# sch5_1.net
KiCad netlist of a schematic drawn in Altium Designer
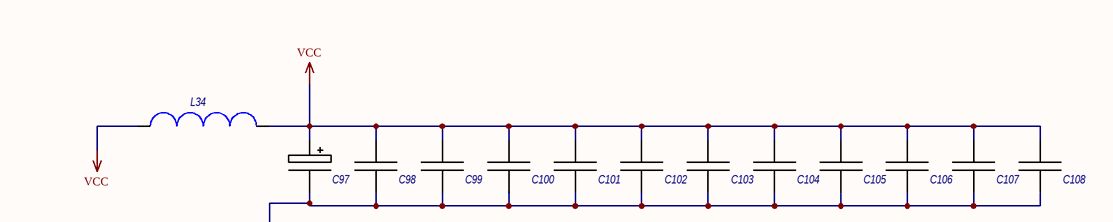
[diagram p0: sch5_1.SchDoc, top left]
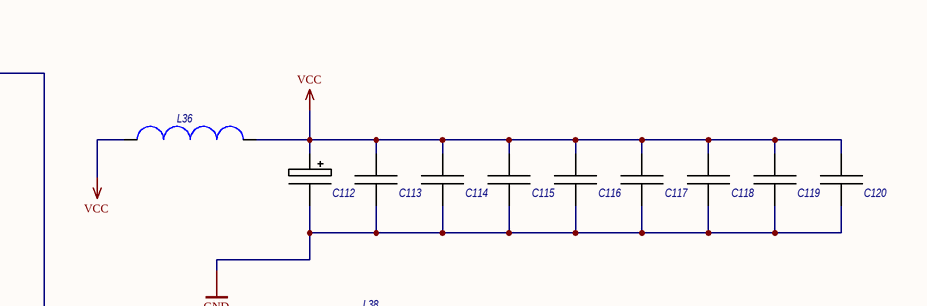
[diagram p1: sch5_1.SchDoc, top right]
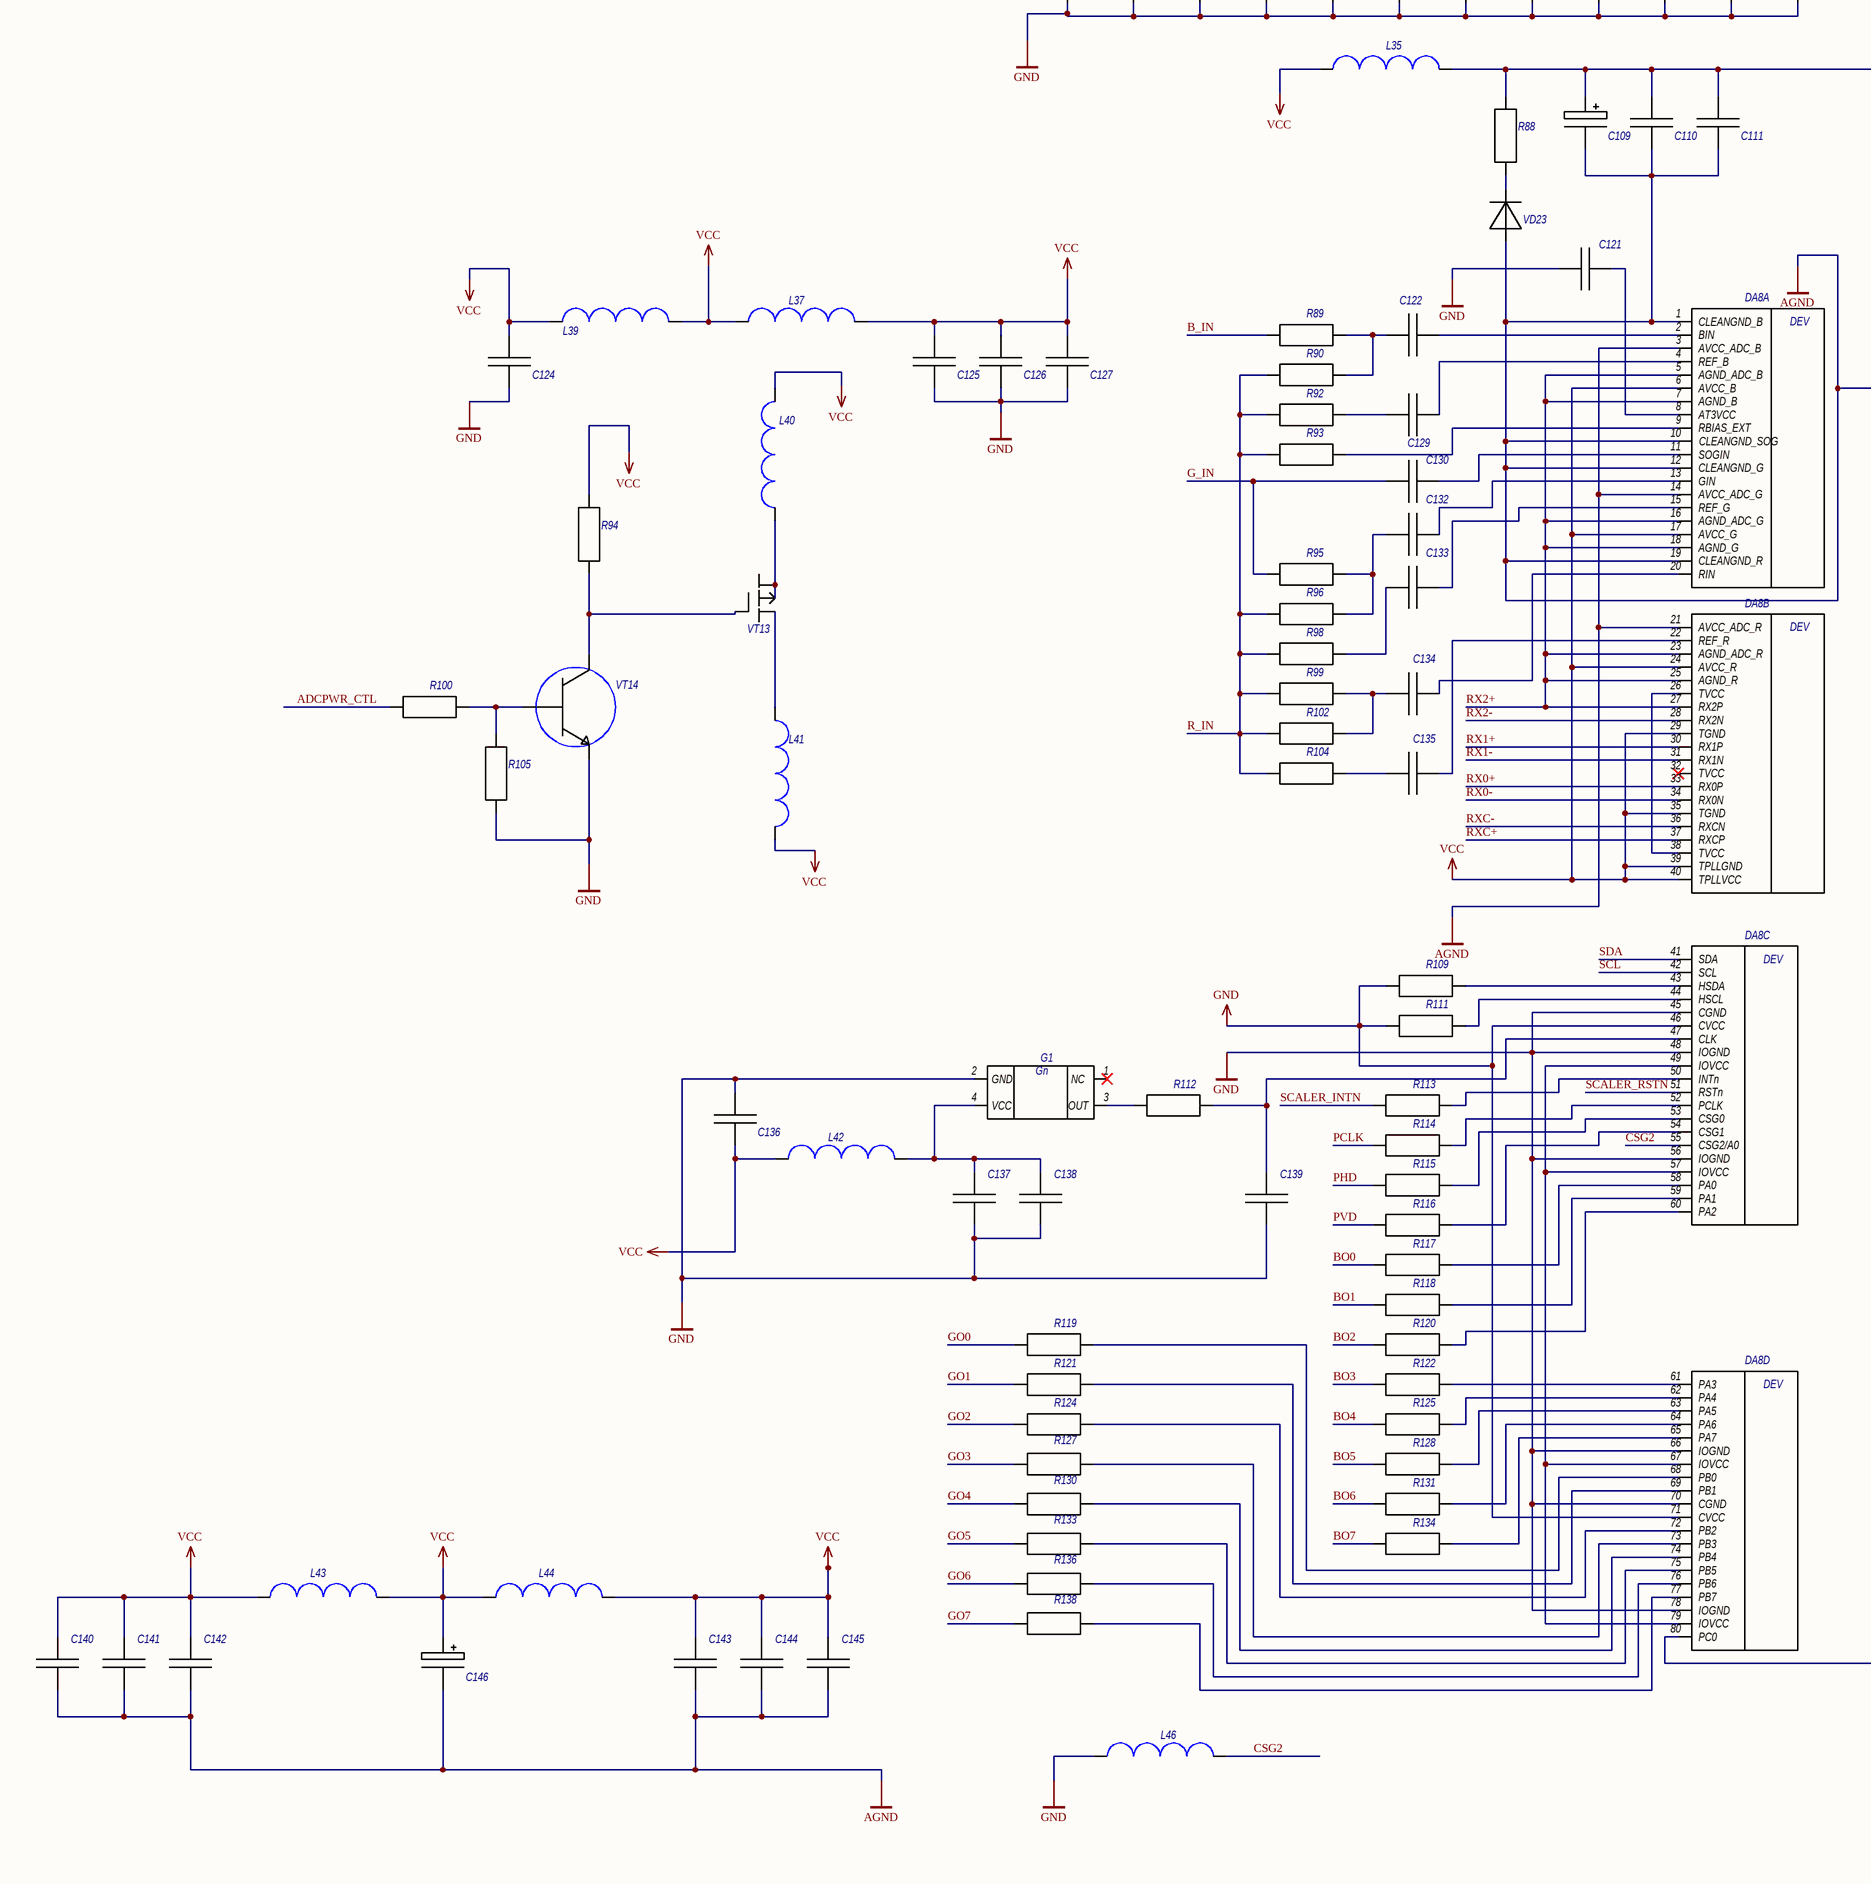
[diagram p2: sch5_1.SchDoc, bottom left]
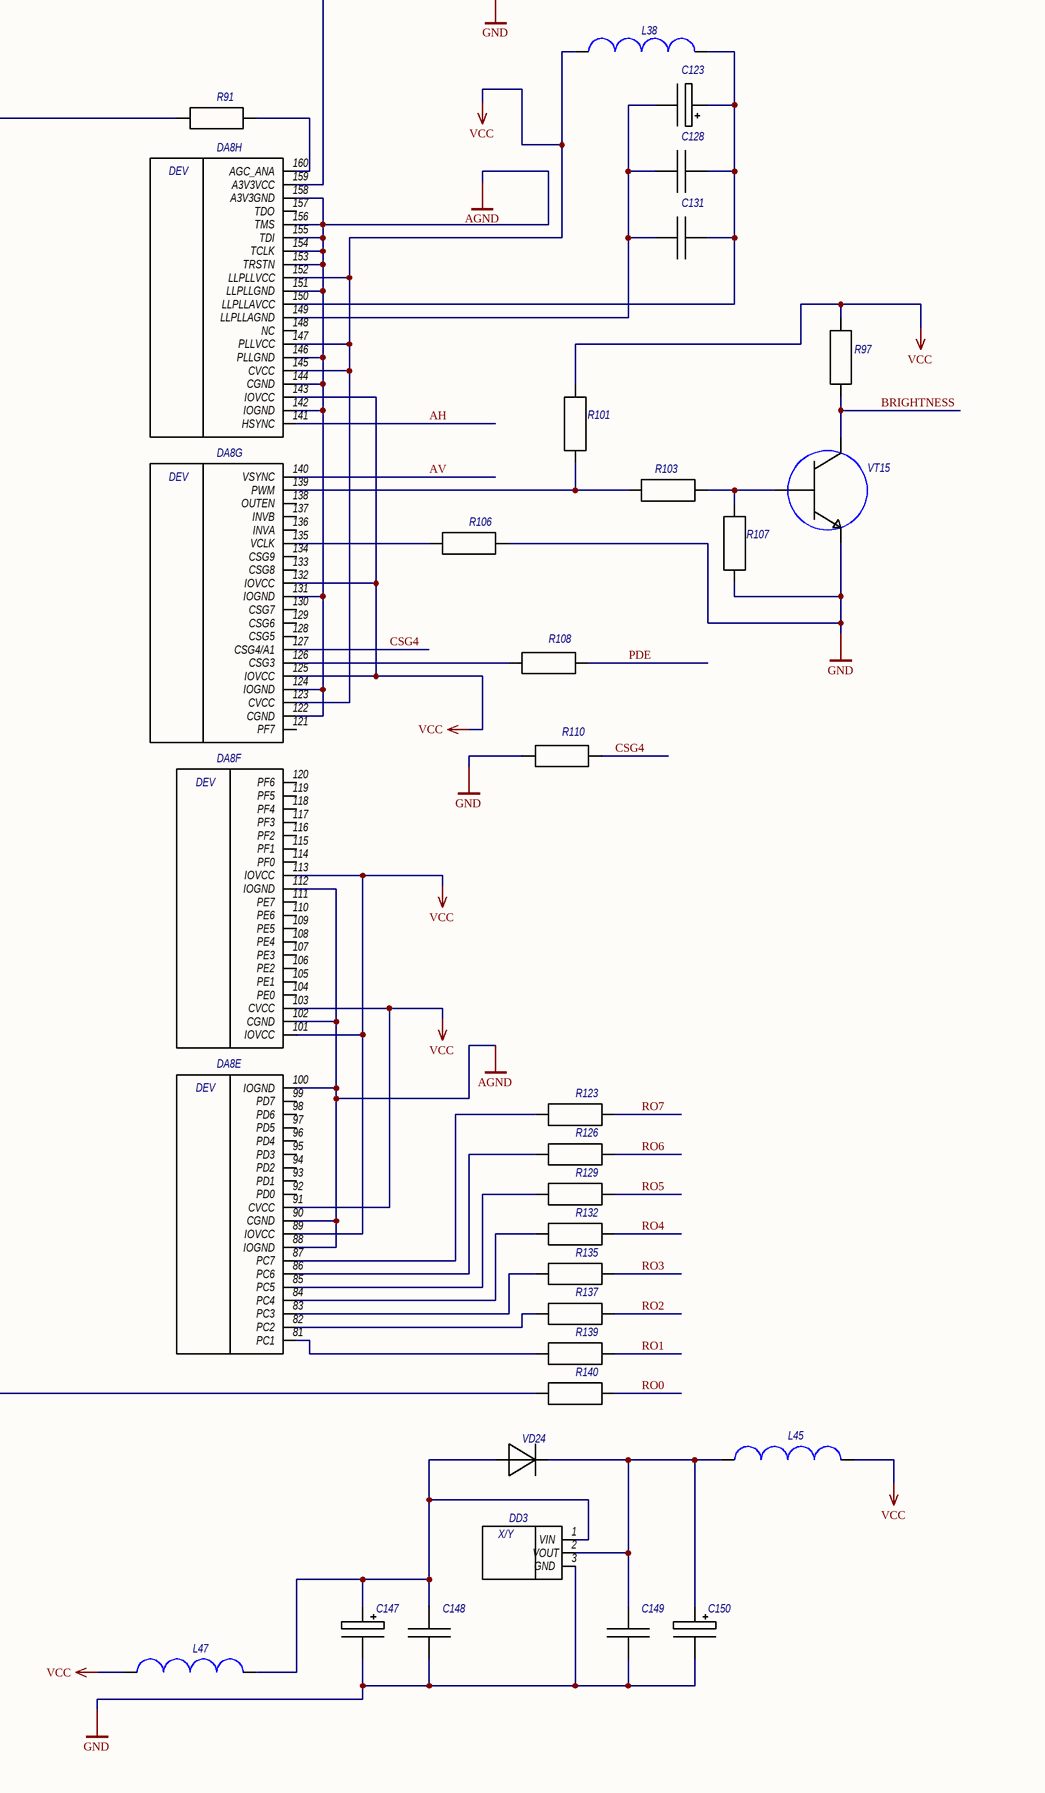
[diagram p3: sch5_1.SchDoc, bottom right]

(export (version "E")
  (design (tool "Eeschema 10.0.6"))
  (components
    (comp (ref "C97")
      (value "*")
      (footprint "Capacitor 0805")
      (libsource (lib "k7shared") (part "Capacitor Duga"))
    )
    (comp (ref "C98")
      (value "*")
      (footprint "Capacitor 0805")
      (libsource (lib "k7shared") (part "Capacitor"))
    )
    (comp (ref "C99")
      (value "*")
      (footprint "Capacitor 0805")
      (libsource (lib "k7shared") (part "Capacitor"))
    )
    (comp (ref "C100")
      (value "*")
      (footprint "Capacitor 0805")
      (libsource (lib "k7shared") (part "Capacitor"))
    )
    (comp (ref "C101")
      (value "*")
      (footprint "Capacitor 0805")
      (libsource (lib "k7shared") (part "Capacitor"))
    )
    (comp (ref "C102")
      (value "*")
      (footprint "Capacitor 0805")
      (libsource (lib "k7shared") (part "Capacitor"))
    )
    (comp (ref "C103")
      (value "*")
      (footprint "Capacitor 0805")
      (libsource (lib "k7shared") (part "Capacitor"))
    )
    (comp (ref "C104")
      (value "*")
      (footprint "Capacitor 0805")
      (libsource (lib "k7shared") (part "Capacitor"))
    )
    (comp (ref "C105")
      (value "*")
      (footprint "Capacitor 0805")
      (libsource (lib "k7shared") (part "Capacitor"))
    )
    (comp (ref "C106")
      (value "*")
      (footprint "Capacitor 0805")
      (libsource (lib "k7shared") (part "Capacitor"))
    )
    (comp (ref "C107")
      (value "*")
      (footprint "Capacitor 0805")
      (libsource (lib "k7shared") (part "Capacitor"))
    )
    (comp (ref "C108")
      (value "*")
      (footprint "Capacitor 0805")
      (libsource (lib "k7shared") (part "Capacitor"))
    )
    (comp (ref "C109")
      (value "*")
      (footprint "Capacitor 0805")
      (libsource (lib "k7shared") (part "Capacitor Duga"))
    )
    (comp (ref "C110")
      (value "*")
      (footprint "Capacitor 0805")
      (libsource (lib "k7shared") (part "Capacitor"))
    )
    (comp (ref "C111")
      (value "*")
      (footprint "Capacitor 0805")
      (libsource (lib "k7shared") (part "Capacitor"))
    )
    (comp (ref "C112")
      (value "*")
      (footprint "Capacitor 0805")
      (libsource (lib "k7shared") (part "Capacitor Duga"))
    )
    (comp (ref "C113")
      (value "*")
      (footprint "Capacitor 0805")
      (libsource (lib "k7shared") (part "Capacitor"))
    )
    (comp (ref "C114")
      (value "*")
      (footprint "Capacitor 0805")
      (libsource (lib "k7shared") (part "Capacitor"))
    )
    (comp (ref "C115")
      (value "*")
      (footprint "Capacitor 0805")
      (libsource (lib "k7shared") (part "Capacitor"))
    )
    (comp (ref "C116")
      (value "*")
      (footprint "Capacitor 0805")
      (libsource (lib "k7shared") (part "Capacitor"))
    )
    (comp (ref "C117")
      (value "*")
      (footprint "Capacitor 0805")
      (libsource (lib "k7shared") (part "Capacitor"))
    )
    (comp (ref "C118")
      (value "*")
      (footprint "Capacitor 0805")
      (libsource (lib "k7shared") (part "Capacitor"))
    )
    (comp (ref "C119")
      (value "*")
      (footprint "Capacitor 0805")
      (libsource (lib "k7shared") (part "Capacitor"))
    )
    (comp (ref "C120")
      (value "*")
      (footprint "Capacitor 0805")
      (libsource (lib "k7shared") (part "Capacitor"))
    )
    (comp (ref "C121")
      (value "*")
      (footprint "Capacitor 0805")
      (libsource (lib "k7shared") (part "Capacitor"))
    )
    (comp (ref "C122")
      (value "*")
      (footprint "Capacitor 0805")
      (libsource (lib "k7shared") (part "Capacitor"))
    )
    (comp (ref "C123")
      (value "*")
      (footprint "Capacitor 0805")
      (libsource (lib "k7shared") (part "Capacitor Duga"))
    )
    (comp (ref "C124")
      (value "*")
      (footprint "Capacitor 0805")
      (libsource (lib "k7shared") (part "Capacitor"))
    )
    (comp (ref "C125")
      (value "*")
      (footprint "Capacitor 0805")
      (libsource (lib "k7shared") (part "Capacitor"))
    )
    (comp (ref "C126")
      (value "*")
      (footprint "Capacitor 0805")
      (libsource (lib "k7shared") (part "Capacitor"))
    )
    (comp (ref "C127")
      (value "*")
      (footprint "Capacitor 0805")
      (libsource (lib "k7shared") (part "Capacitor"))
    )
    (comp (ref "C128")
      (value "*")
      (footprint "Capacitor 0805")
      (libsource (lib "k7shared") (part "Capacitor"))
    )
    (comp (ref "C129")
      (value "*")
      (footprint "Capacitor 0805")
      (libsource (lib "k7shared") (part "Capacitor"))
    )
    (comp (ref "C130")
      (value "*")
      (footprint "Capacitor 0805")
      (libsource (lib "k7shared") (part "Capacitor"))
    )
    (comp (ref "C131")
      (value "*")
      (footprint "Capacitor 0805")
      (libsource (lib "k7shared") (part "Capacitor"))
    )
    (comp (ref "C132")
      (value "*")
      (footprint "Capacitor 0805")
      (libsource (lib "k7shared") (part "Capacitor"))
    )
    (comp (ref "C133")
      (value "*")
      (footprint "Capacitor 0805")
      (libsource (lib "k7shared") (part "Capacitor"))
    )
    (comp (ref "C134")
      (value "*")
      (footprint "Capacitor 0805")
      (libsource (lib "k7shared") (part "Capacitor"))
    )
    (comp (ref "C135")
      (value "*")
      (footprint "Capacitor 0805")
      (libsource (lib "k7shared") (part "Capacitor"))
    )
    (comp (ref "C136")
      (value "*")
      (footprint "Capacitor 0805")
      (libsource (lib "k7shared") (part "Capacitor"))
    )
    (comp (ref "C137")
      (value "*")
      (footprint "Capacitor 0805")
      (libsource (lib "k7shared") (part "Capacitor"))
    )
    (comp (ref "C138")
      (value "*")
      (footprint "Capacitor 0805")
      (libsource (lib "k7shared") (part "Capacitor"))
    )
    (comp (ref "C139")
      (value "*")
      (footprint "Capacitor 0805")
      (libsource (lib "k7shared") (part "Capacitor"))
    )
    (comp (ref "C140")
      (value "*")
      (footprint "Capacitor 0805")
      (libsource (lib "k7shared") (part "Capacitor"))
    )
    (comp (ref "C141")
      (value "*")
      (footprint "Capacitor 0805")
      (libsource (lib "k7shared") (part "Capacitor"))
    )
    (comp (ref "C142")
      (value "*")
      (footprint "Capacitor 0805")
      (libsource (lib "k7shared") (part "Capacitor"))
    )
    (comp (ref "C143")
      (value "*")
      (footprint "Capacitor 0805")
      (libsource (lib "k7shared") (part "Capacitor"))
    )
    (comp (ref "C144")
      (value "*")
      (footprint "Capacitor 0805")
      (libsource (lib "k7shared") (part "Capacitor"))
    )
    (comp (ref "C145")
      (value "*")
      (footprint "Capacitor 0805")
      (libsource (lib "k7shared") (part "Capacitor"))
    )
    (comp (ref "C146")
      (value "*")
      (footprint "Capacitor 0805")
      (libsource (lib "k7shared") (part "Capacitor Duga"))
    )
    (comp (ref "C147")
      (value "*")
      (footprint "Capacitor 0805")
      (libsource (lib "k7shared") (part "Capacitor Duga"))
    )
    (comp (ref "C148")
      (value "*")
      (footprint "Capacitor 0805")
      (libsource (lib "k7shared") (part "Capacitor"))
    )
    (comp (ref "C149")
      (value "*")
      (footprint "Capacitor 0805")
      (libsource (lib "k7shared") (part "Capacitor"))
    )
    (comp (ref "C150")
      (value "*")
      (footprint "Capacitor 0805")
      (libsource (lib "k7shared") (part "Capacitor Duga"))
    )
    (comp (ref "DA8") (value "*") (footprint "OMG_1") (libsource (lib "k7sch5") (part "OMG")))
    (comp (ref "DD3") (value "*") (footprint "MIC39") (libsource (lib "k7sch5") (part "MIC39")))
    (comp (ref "G1") (value "*") (footprint "GENERATOR-25MHZ") (libsource (lib "k7sch5") (part "MHZ25")))
    (comp (ref "L34") (value "*") (footprint "Inductor 2520") (libsource (lib "k7shared") (part "Inductor")))
    (comp (ref "L35") (value "*") (footprint "Inductor 2520") (libsource (lib "k7shared") (part "Inductor")))
    (comp (ref "L36") (value "*") (footprint "Inductor 2520") (libsource (lib "k7shared") (part "Inductor")))
    (comp (ref "L37") (value "*") (footprint "Inductor 2520") (libsource (lib "k7shared") (part "Inductor")))
    (comp (ref "L38") (value "*") (footprint "Inductor 2520") (libsource (lib "k7shared") (part "Inductor")))
    (comp (ref "L39") (value "*") (footprint "Inductor 2520") (libsource (lib "k7shared") (part "Inductor")))
    (comp (ref "L40") (value "*") (footprint "Inductor 2520") (libsource (lib "") (part "Inductor_1")))
    (comp (ref "L41") (value "*") (footprint "Inductor 2520") (libsource (lib "") (part "Inductor_1")))
    (comp (ref "L42") (value "*") (footprint "Inductor 2520") (libsource (lib "k7shared") (part "Inductor")))
    (comp (ref "L43") (value "*") (footprint "Inductor 2520") (libsource (lib "k7shared") (part "Inductor")))
    (comp (ref "L44") (value "*") (footprint "Inductor 2520") (libsource (lib "k7shared") (part "Inductor")))
    (comp (ref "L45") (value "*") (footprint "Inductor 2520") (libsource (lib "k7shared") (part "Inductor")))
    (comp (ref "L46") (value "*") (footprint "Inductor 2520") (libsource (lib "k7shared") (part "Inductor")))
    (comp (ref "L47") (value "*") (footprint "Inductor 2520") (libsource (lib "k7shared") (part "Inductor")))
    (comp (ref "R88") (value "*") (footprint "Resistor 1206") (libsource (lib "k7shared") (part "Resistor")))
    (comp (ref "R89") (value "*") (footprint "Resistor 1206") (libsource (lib "k7shared") (part "Resistor")))
    (comp (ref "R90") (value "*") (footprint "Resistor 1206") (libsource (lib "k7shared") (part "Resistor")))
    (comp (ref "R91") (value "*") (footprint "Resistor 1206") (libsource (lib "k7shared") (part "Resistor")))
    (comp (ref "R92") (value "*") (footprint "Resistor 1206") (libsource (lib "k7shared") (part "Resistor")))
    (comp (ref "R93") (value "*") (footprint "Resistor 1206") (libsource (lib "k7shared") (part "Resistor")))
    (comp (ref "R94") (value "*") (footprint "Resistor 1206") (libsource (lib "k7shared") (part "Resistor")))
    (comp (ref "R95") (value "*") (footprint "Resistor 1206") (libsource (lib "k7shared") (part "Resistor")))
    (comp (ref "R96") (value "*") (footprint "Resistor 1206") (libsource (lib "k7shared") (part "Resistor")))
    (comp (ref "R97") (value "*") (footprint "Resistor 1206") (libsource (lib "k7shared") (part "Resistor")))
    (comp (ref "R98") (value "*") (footprint "Resistor 1206") (libsource (lib "k7shared") (part "Resistor")))
    (comp (ref "R99") (value "*") (footprint "Resistor 1206") (libsource (lib "k7shared") (part "Resistor")))
    (comp (ref "R100") (value "*") (footprint "Resistor 1206") (libsource (lib "k7shared") (part "Resistor")))
    (comp (ref "R101") (value "*") (footprint "Resistor 1206") (libsource (lib "k7shared") (part "Resistor")))
    (comp (ref "R102") (value "*") (footprint "Resistor 1206") (libsource (lib "k7shared") (part "Resistor")))
    (comp (ref "R103") (value "*") (footprint "Resistor 1206") (libsource (lib "k7shared") (part "Resistor")))
    (comp (ref "R104") (value "*") (footprint "Resistor 1206") (libsource (lib "k7shared") (part "Resistor")))
    (comp (ref "R105") (value "*") (footprint "Resistor 1206") (libsource (lib "k7shared") (part "Resistor")))
    (comp (ref "R106") (value "*") (footprint "Resistor 1206") (libsource (lib "k7shared") (part "Resistor")))
    (comp (ref "R107") (value "*") (footprint "Resistor 1206") (libsource (lib "k7shared") (part "Resistor")))
    (comp (ref "R108") (value "*") (footprint "Resistor 1206") (libsource (lib "k7shared") (part "Resistor")))
    (comp (ref "R109") (value "*") (footprint "Resistor 1206") (libsource (lib "k7shared") (part "Resistor")))
    (comp (ref "R110") (value "*") (footprint "Resistor 1206") (libsource (lib "k7shared") (part "Resistor")))
    (comp (ref "R111") (value "*") (footprint "Resistor 1206") (libsource (lib "k7shared") (part "Resistor")))
    (comp (ref "R112") (value "*") (footprint "Resistor 1206") (libsource (lib "k7shared") (part "Resistor")))
    (comp (ref "R113") (value "*") (footprint "Resistor 1206") (libsource (lib "k7shared") (part "Resistor")))
    (comp (ref "R114") (value "*") (footprint "Resistor 1206") (libsource (lib "k7shared") (part "Resistor")))
    (comp (ref "R115") (value "*") (footprint "Resistor 1206") (libsource (lib "k7shared") (part "Resistor")))
    (comp (ref "R116") (value "*") (footprint "Resistor 1206") (libsource (lib "k7shared") (part "Resistor")))
    (comp (ref "R117") (value "*") (footprint "Resistor 1206") (libsource (lib "k7shared") (part "Resistor")))
    (comp (ref "R118") (value "*") (footprint "Resistor 1206") (libsource (lib "k7shared") (part "Resistor")))
    (comp (ref "R119") (value "*") (footprint "Resistor 1206") (libsource (lib "k7shared") (part "Resistor")))
    (comp (ref "R120") (value "*") (footprint "Resistor 1206") (libsource (lib "k7shared") (part "Resistor")))
    (comp (ref "R121") (value "*") (footprint "Resistor 1206") (libsource (lib "k7shared") (part "Resistor")))
    (comp (ref "R122") (value "*") (footprint "Resistor 1206") (libsource (lib "k7shared") (part "Resistor")))
    (comp (ref "R123") (value "*") (footprint "Resistor 1206") (libsource (lib "k7shared") (part "Resistor")))
    (comp (ref "R124") (value "*") (footprint "Resistor 1206") (libsource (lib "k7shared") (part "Resistor")))
    (comp (ref "R125") (value "*") (footprint "Resistor 1206") (libsource (lib "k7shared") (part "Resistor")))
    (comp (ref "R126") (value "*") (footprint "Resistor 1206") (libsource (lib "k7shared") (part "Resistor")))
    (comp (ref "R127") (value "*") (footprint "Resistor 1206") (libsource (lib "k7shared") (part "Resistor")))
    (comp (ref "R128") (value "*") (footprint "Resistor 1206") (libsource (lib "k7shared") (part "Resistor")))
    (comp (ref "R129") (value "*") (footprint "Resistor 1206") (libsource (lib "k7shared") (part "Resistor")))
    (comp (ref "R130") (value "*") (footprint "Resistor 1206") (libsource (lib "k7shared") (part "Resistor")))
    (comp (ref "R131") (value "*") (footprint "Resistor 1206") (libsource (lib "k7shared") (part "Resistor")))
    (comp (ref "R132") (value "*") (footprint "Resistor 1206") (libsource (lib "k7shared") (part "Resistor")))
    (comp (ref "R133") (value "*") (footprint "Resistor 1206") (libsource (lib "k7shared") (part "Resistor")))
    (comp (ref "R134") (value "*") (footprint "Resistor 1206") (libsource (lib "k7shared") (part "Resistor")))
    (comp (ref "R135") (value "*") (footprint "Resistor 1206") (libsource (lib "k7shared") (part "Resistor")))
    (comp (ref "R136") (value "*") (footprint "Resistor 1206") (libsource (lib "k7shared") (part "Resistor")))
    (comp (ref "R137") (value "*") (footprint "Resistor 1206") (libsource (lib "k7shared") (part "Resistor")))
    (comp (ref "R138") (value "*") (footprint "Resistor 1206") (libsource (lib "k7shared") (part "Resistor")))
    (comp (ref "R139") (value "*") (footprint "Resistor 1206") (libsource (lib "k7shared") (part "Resistor")))
    (comp (ref "R140") (value "*") (footprint "Resistor 1206") (libsource (lib "k7shared") (part "Resistor")))
    (comp (ref "VD23") (value "*") (footprint "Diode") (libsource (lib "k7shared") (part "Diode 1")))
    (comp (ref "VD24") (value "*") (footprint "Diode") (libsource (lib "k7shared") (part "Diode 1")))
    (comp (ref "VT13")
      (value "MOP TRANSISTOR")
      (footprint "TR")
      (libsource (lib "k7shared") (part "MOP TRANSISTOR"))
    )
    (comp (ref "VT14")
      (value "*")
      (footprint "Transistor 1")
      (libsource (lib "k7shared") (part "Transistor 1"))
    )
    (comp (ref "VT15")
      (value "*")
      (footprint "Transistor 1")
      (libsource (lib "k7shared") (part "Transistor 1"))
    )
  )
  (nets
    (net (code "1") (name "/ADCPWR_CTL") (class "Default")
      (node (ref "R100") (pin "1") (pinfunction "1_1") (pintype "passive"))
    )
    (net (code "2") (name "/AH") (class "Default")
      (node (ref "DA8") (pin "141") (pinfunction "HSYNC_141") (pintype "passive"))
    )
    (net (code "3") (name "/AV") (class "Default")
      (node (ref "DA8") (pin "140") (pinfunction "VSYNC_140") (pintype "passive"))
    )
    (net (code "4") (name "/BO0") (class "Default")
      (node (ref "R117") (pin "1") (pinfunction "1_1") (pintype "passive"))
    )
    (net (code "5") (name "/BO1") (class "Default")
      (node (ref "R118") (pin "1") (pinfunction "1_1") (pintype "passive"))
    )
    (net (code "6") (name "/BO2") (class "Default")
      (node (ref "R120") (pin "1") (pinfunction "1_1") (pintype "passive"))
    )
    (net (code "7") (name "/BO3") (class "Default")
      (node (ref "R122") (pin "1") (pinfunction "1_1") (pintype "passive"))
    )
    (net (code "8") (name "/BO4") (class "Default")
      (node (ref "R125") (pin "1") (pinfunction "1_1") (pintype "passive"))
    )
    (net (code "9") (name "/BO5") (class "Default")
      (node (ref "R128") (pin "1") (pinfunction "1_1") (pintype "passive"))
    )
    (net (code "10") (name "/BO6") (class "Default")
      (node (ref "R131") (pin "1") (pinfunction "1_1") (pintype "passive"))
    )
    (net (code "11") (name "/BO7") (class "Default")
      (node (ref "R134") (pin "1") (pinfunction "1_1") (pintype "passive"))
    )
    (net (code "12") (name "/BRIGHTNESS") (class "Default")
      (node (ref "R97") (pin "1") (pinfunction "1_1") (pintype "passive"))
      (node (ref "VT15") (pin "2") (pinfunction "EMITTER_2") (pintype "passive"))
    )
    (net (code "13") (name "/B_IN") (class "Default")
      (node (ref "R89") (pin "1") (pinfunction "1_1") (pintype "passive"))
    )
    (net (code "14") (name "/CSG2") (class "Default")
      (node (ref "DA8") (pin "55") (pinfunction "CSG2/A0_55") (pintype "passive"))
      (node (ref "L46") (pin "2") (pinfunction "2_2") (pintype "passive"))
    )
    (net (code "15") (name "/CSG4") (class "Default")
      (node (ref "DA8") (pin "127") (pinfunction "CSG4/A1_127") (pintype "passive"))
      (node (ref "R110") (pin "2") (pinfunction "2_2") (pintype "passive"))
    )
    (net (code "16") (name "/GO0") (class "Default")
      (node (ref "R119") (pin "1") (pinfunction "1_1") (pintype "passive"))
    )
    (net (code "17") (name "/GO1") (class "Default")
      (node (ref "R121") (pin "1") (pinfunction "1_1") (pintype "passive"))
    )
    (net (code "18") (name "/GO2") (class "Default")
      (node (ref "R124") (pin "1") (pinfunction "1_1") (pintype "passive"))
    )
    (net (code "19") (name "/GO3") (class "Default")
      (node (ref "R127") (pin "1") (pinfunction "1_1") (pintype "passive"))
    )
    (net (code "20") (name "/GO4") (class "Default")
      (node (ref "R130") (pin "1") (pinfunction "1_1") (pintype "passive"))
    )
    (net (code "21") (name "/GO5") (class "Default")
      (node (ref "R133") (pin "1") (pinfunction "1_1") (pintype "passive"))
    )
    (net (code "22") (name "/GO6") (class "Default")
      (node (ref "R136") (pin "1") (pinfunction "1_1") (pintype "passive"))
    )
    (net (code "23") (name "/GO7") (class "Default")
      (node (ref "R138") (pin "1") (pinfunction "1_1") (pintype "passive"))
    )
    (net (code "24") (name "/G_IN") (class "Default")
      (node (ref "C130") (pin "2") (pinfunction "2_2") (pintype "passive"))
      (node (ref "R95") (pin "1") (pinfunction "1_1") (pintype "passive"))
    )
    (net (code "25") (name "/PCLK") (class "Default")
      (node (ref "R114") (pin "1") (pinfunction "1_1") (pintype "passive"))
    )
    (net (code "26") (name "/PDE") (class "Default")
      (node (ref "R108") (pin "2") (pinfunction "2_2") (pintype "passive"))
    )
    (net (code "27") (name "/PHD") (class "Default")
      (node (ref "R115") (pin "1") (pinfunction "1_1") (pintype "passive"))
    )
    (net (code "28") (name "/PVD") (class "Default")
      (node (ref "R116") (pin "1") (pinfunction "1_1") (pintype "passive"))
    )
    (net (code "29") (name "/RO0") (class "Default")
      (node (ref "R140") (pin "2") (pinfunction "2_2") (pintype "passive"))
    )
    (net (code "30") (name "/RO1") (class "Default")
      (node (ref "R139") (pin "2") (pinfunction "2_2") (pintype "passive"))
    )
    (net (code "31") (name "/RO2") (class "Default")
      (node (ref "R137") (pin "2") (pinfunction "2_2") (pintype "passive"))
    )
    (net (code "32") (name "/RO3") (class "Default")
      (node (ref "R135") (pin "2") (pinfunction "2_2") (pintype "passive"))
    )
    (net (code "33") (name "/RO4") (class "Default")
      (node (ref "R132") (pin "2") (pinfunction "2_2") (pintype "passive"))
    )
    (net (code "34") (name "/RO5") (class "Default")
      (node (ref "R129") (pin "2") (pinfunction "2_2") (pintype "passive"))
    )
    (net (code "35") (name "/RO6") (class "Default")
      (node (ref "R126") (pin "2") (pinfunction "2_2") (pintype "passive"))
    )
    (net (code "36") (name "/RO7") (class "Default")
      (node (ref "R123") (pin "2") (pinfunction "2_2") (pintype "passive"))
    )
    (net (code "37") (name "/RX0+") (class "Default")
      (node (ref "DA8") (pin "33") (pinfunction "RX0P_33") (pintype "passive"))
    )
    (net (code "38") (name "/RX0-") (class "Default")
      (node (ref "DA8") (pin "34") (pinfunction "RX0N_34") (pintype "passive"))
    )
    (net (code "39") (name "/RX1+") (class "Default")
      (node (ref "DA8") (pin "30") (pinfunction "RX1P_30") (pintype "passive"))
    )
    (net (code "40") (name "/RX1-") (class "Default")
      (node (ref "DA8") (pin "31") (pinfunction "RX1N_31") (pintype "passive"))
    )
    (net (code "41") (name "/RX2+") (class "Default")
      (node (ref "DA8") (pin "16") (pinfunction "AGND_ADC_G_16") (pintype "passive"))
      (node (ref "DA8") (pin "18") (pinfunction "AGND_G_18") (pintype "passive"))
      (node (ref "DA8") (pin "23") (pinfunction "AGND_ADC_R_23") (pintype "passive"))
      (node (ref "DA8") (pin "25") (pinfunction "AGND_R_25") (pintype "passive"))
      (node (ref "DA8") (pin "27") (pinfunction "RX2P_27") (pintype "passive"))
      (node (ref "DA8") (pin "5") (pinfunction "AGND_ADC_B_5") (pintype "passive"))
      (node (ref "DA8") (pin "7") (pinfunction "AGND_B_7") (pintype "passive"))
    )
    (net (code "42") (name "/RX2-") (class "Default")
      (node (ref "DA8") (pin "28") (pinfunction "RX2N_28") (pintype "passive"))
    )
    (net (code "43") (name "/RXC+") (class "Default")
      (node (ref "DA8") (pin "37") (pinfunction "RXCP_37") (pintype "passive"))
    )
    (net (code "44") (name "/RXC-") (class "Default")
      (node (ref "DA8") (pin "36") (pinfunction "RXCN_36") (pintype "passive"))
    )
    (net (code "45") (name "/R_IN") (class "Default")
      (node (ref "R102") (pin "1") (pinfunction "1_1") (pintype "passive"))
      (node (ref "R104") (pin "1") (pinfunction "1_1") (pintype "passive"))
      (node (ref "R90") (pin "1") (pinfunction "1_1") (pintype "passive"))
      (node (ref "R92") (pin "1") (pinfunction "1_1") (pintype "passive"))
      (node (ref "R93") (pin "1") (pinfunction "1_1") (pintype "passive"))
      (node (ref "R96") (pin "1") (pinfunction "1_1") (pintype "passive"))
      (node (ref "R98") (pin "1") (pinfunction "1_1") (pintype "passive"))
      (node (ref "R99") (pin "1") (pinfunction "1_1") (pintype "passive"))
    )
    (net (code "46") (name "/SCALER_INTN") (class "Default")
      (node (ref "R113") (pin "1") (pinfunction "1_1") (pintype "passive"))
    )
    (net (code "47") (name "/SCALER_RSTN") (class "Default")
      (node (ref "DA8") (pin "51") (pinfunction "RSTn_51") (pintype "passive"))
    )
    (net (code "48") (name "/SCL") (class "Default")
      (node (ref "DA8") (pin "42") (pinfunction "SCL_42") (pintype "passive"))
    )
    (net (code "49") (name "/SDA") (class "Default")
      (node (ref "DA8") (pin "41") (pinfunction "SDA_41") (pintype "passive"))
    )
    (net (code "50") (name "AGND") (class "Default")
      (node (ref "C109") (pin "1") (pinfunction "1_1") (pintype "passive"))
      (node (ref "C110") (pin "1") (pinfunction "1_1") (pintype "passive"))
      (node (ref "C111") (pin "1") (pinfunction "1_1") (pintype "passive"))
      (node (ref "C140") (pin "1") (pinfunction "1_1") (pintype "passive"))
      (node (ref "C141") (pin "1") (pinfunction "1_1") (pintype "passive"))
      (node (ref "C142") (pin "1") (pinfunction "1_1") (pintype "passive"))
      (node (ref "C143") (pin "1") (pinfunction "1_1") (pintype "passive"))
      (node (ref "C144") (pin "1") (pinfunction "1_1") (pintype "passive"))
      (node (ref "C145") (pin "1") (pinfunction "1_1") (pintype "passive"))
      (node (ref "C146") (pin "1") (pinfunction "1_1") (pintype "passive"))
      (node (ref "DA8") (pin "1") (pinfunction "CLEANGND_B_1") (pintype "passive"))
      (node (ref "DA8") (pin "10") (pinfunction "CLEANGND_SOG_10") (pintype "passive"))
      (node (ref "DA8") (pin "100") (pinfunction "IOGND_100") (pintype "passive"))
      (node (ref "DA8") (pin "102") (pinfunction "CGND_102") (pintype "passive"))
      (node (ref "DA8") (pin "112") (pinfunction "IOGND_112") (pintype "passive"))
      (node (ref "DA8") (pin "12") (pinfunction "CLEANGND_G_12") (pintype "passive"))
      (node (ref "DA8") (pin "122") (pinfunction "CGND_122") (pintype "passive"))
      (node (ref "DA8") (pin "124") (pinfunction "IOGND_124") (pintype "passive"))
      (node (ref "DA8") (pin "131") (pinfunction "IOGND_131") (pintype "passive"))
      (node (ref "DA8") (pin "14") (pinfunction "AVCC_ADC_G_14") (pintype "passive"))
      (node (ref "DA8") (pin "142") (pinfunction "IOGND_142") (pintype "passive"))
      (node (ref "DA8") (pin "144") (pinfunction "CGND_144") (pintype "passive"))
      (node (ref "DA8") (pin "146") (pinfunction "PLLGND_146") (pintype "passive"))
      (node (ref "DA8") (pin "151") (pinfunction "LLPLLGND_151") (pintype "passive"))
      (node (ref "DA8") (pin "153") (pinfunction "TRSTN_153") (pintype "passive"))
      (node (ref "DA8") (pin "154") (pinfunction "TCLK_154") (pintype "passive"))
      (node (ref "DA8") (pin "155") (pinfunction "TDI_155") (pintype "passive"))
      (node (ref "DA8") (pin "156") (pinfunction "TMS_156") (pintype "passive"))
      (node (ref "DA8") (pin "158") (pinfunction "A3V3GND_158") (pintype "passive"))
      (node (ref "DA8") (pin "19") (pinfunction "CLEANGND_R_19") (pintype "passive"))
      (node (ref "DA8") (pin "21") (pinfunction "AVCC_ADC_R_21") (pintype "passive"))
      (node (ref "DA8") (pin "3") (pinfunction "AVCC_ADC_B_3") (pintype "passive"))
      (node (ref "DA8") (pin "88") (pinfunction "IOGND_88") (pintype "passive"))
      (node (ref "DA8") (pin "90") (pinfunction "CGND_90") (pintype "passive"))
      (node (ref "R91") (pin "1") (pinfunction "1_1") (pintype "passive"))
      (node (ref "VD23") (pin "1") (pinfunction "1_1") (pintype "passive"))
    )
    (net (code "51") (name "GND") (class "Default")
      (node (ref "C100") (pin "1") (pinfunction "1_1") (pintype "passive"))
      (node (ref "C101") (pin "1") (pinfunction "1_1") (pintype "passive"))
      (node (ref "C102") (pin "1") (pinfunction "1_1") (pintype "passive"))
      (node (ref "C103") (pin "1") (pinfunction "1_1") (pintype "passive"))
      (node (ref "C104") (pin "1") (pinfunction "1_1") (pintype "passive"))
      (node (ref "C105") (pin "1") (pinfunction "1_1") (pintype "passive"))
      (node (ref "C106") (pin "1") (pinfunction "1_1") (pintype "passive"))
      (node (ref "C107") (pin "1") (pinfunction "1_1") (pintype "passive"))
      (node (ref "C108") (pin "1") (pinfunction "1_1") (pintype "passive"))
      (node (ref "C112") (pin "1") (pinfunction "1_1") (pintype "passive"))
      (node (ref "C113") (pin "1") (pinfunction "1_1") (pintype "passive"))
      (node (ref "C114") (pin "1") (pinfunction "1_1") (pintype "passive"))
      (node (ref "C115") (pin "1") (pinfunction "1_1") (pintype "passive"))
      (node (ref "C116") (pin "1") (pinfunction "1_1") (pintype "passive"))
      (node (ref "C117") (pin "1") (pinfunction "1_1") (pintype "passive"))
      (node (ref "C118") (pin "1") (pinfunction "1_1") (pintype "passive"))
      (node (ref "C119") (pin "1") (pinfunction "1_1") (pintype "passive"))
      (node (ref "C120") (pin "1") (pinfunction "1_1") (pintype "passive"))
      (node (ref "C121") (pin "2") (pinfunction "2_2") (pintype "passive"))
      (node (ref "C124") (pin "1") (pinfunction "1_1") (pintype "passive"))
      (node (ref "C125") (pin "1") (pinfunction "1_1") (pintype "passive"))
      (node (ref "C126") (pin "1") (pinfunction "1_1") (pintype "passive"))
      (node (ref "C127") (pin "1") (pinfunction "1_1") (pintype "passive"))
      (node (ref "C136") (pin "2") (pinfunction "2_2") (pintype "passive"))
      (node (ref "C137") (pin "1") (pinfunction "1_1") (pintype "passive"))
      (node (ref "C138") (pin "1") (pinfunction "1_1") (pintype "passive"))
      (node (ref "C139") (pin "1") (pinfunction "1_1") (pintype "passive"))
      (node (ref "C147") (pin "1") (pinfunction "1_1") (pintype "passive"))
      (node (ref "C148") (pin "1") (pinfunction "1_1") (pintype "passive"))
      (node (ref "C149") (pin "1") (pinfunction "1_1") (pintype "passive"))
      (node (ref "C150") (pin "1") (pinfunction "1_1") (pintype "passive"))
      (node (ref "C97") (pin "1") (pinfunction "1_1") (pintype "passive"))
      (node (ref "C98") (pin "1") (pinfunction "1_1") (pintype "passive"))
      (node (ref "C99") (pin "1") (pinfunction "1_1") (pintype "passive"))
      (node (ref "DA8") (pin "45") (pinfunction "CGND_45") (pintype "passive"))
      (node (ref "DA8") (pin "46") (pinfunction "CVCC_46") (pintype "passive"))
      (node (ref "DA8") (pin "48") (pinfunction "IOGND_48") (pintype "passive"))
      (node (ref "DA8") (pin "56") (pinfunction "IOGND_56") (pintype "passive"))
      (node (ref "DA8") (pin "66") (pinfunction "IOGND_66") (pintype "passive"))
      (node (ref "DA8") (pin "70") (pinfunction "CGND_70") (pintype "passive"))
      (node (ref "DA8") (pin "71") (pinfunction "CVCC_71") (pintype "passive"))
      (node (ref "DA8") (pin "78") (pinfunction "IOGND_78") (pintype "passive"))
      (node (ref "DD3") (pin "3") (pinfunction "GND_3") (pintype "passive"))
      (node (ref "G1") (pin "2") (pinfunction "GND_2") (pintype "passive"))
      (node (ref "L46") (pin "1") (pinfunction "1_1") (pintype "passive"))
      (node (ref "R105") (pin "1") (pinfunction "1_1") (pintype "passive"))
      (node (ref "R106") (pin "2") (pinfunction "2_2") (pintype "passive"))
      (node (ref "R107") (pin "1") (pinfunction "1_1") (pintype "passive"))
      (node (ref "R109") (pin "1") (pinfunction "1_1") (pintype "passive"))
      (node (ref "R110") (pin "1") (pinfunction "1_1") (pintype "passive"))
      (node (ref "R111") (pin "1") (pinfunction "1_1") (pintype "passive"))
      (node (ref "VT14") (pin "1") (pinfunction "KOLLECTOR_1") (pintype "passive"))
      (node (ref "VT15") (pin "1") (pinfunction "KOLLECTOR_1") (pintype "passive"))
    )
    (net (code "52") (name "Net-(C122-Pad2)") (class "Default")
      (node (ref "C122") (pin "2") (pinfunction "2_2") (pintype "passive"))
      (node (ref "R89") (pin "2") (pinfunction "2_2") (pintype "passive"))
      (node (ref "R90") (pin "2") (pinfunction "2_2") (pintype "passive"))
    )
    (net (code "53") (name "Net-(C129-Pad2)") (class "Default")
      (node (ref "C129") (pin "2") (pinfunction "2_2") (pintype "passive"))
      (node (ref "R92") (pin "2") (pinfunction "2_2") (pintype "passive"))
    )
    (net (code "54") (name "Net-(C132-Pad2)") (class "Default")
      (node (ref "C132") (pin "2") (pinfunction "2_2") (pintype "passive"))
      (node (ref "R95") (pin "2") (pinfunction "2_2") (pintype "passive"))
      (node (ref "R96") (pin "2") (pinfunction "2_2") (pintype "passive"))
    )
    (net (code "55") (name "Net-(C133-Pad2)") (class "Default")
      (node (ref "C133") (pin "2") (pinfunction "2_2") (pintype "passive"))
      (node (ref "R98") (pin "2") (pinfunction "2_2") (pintype "passive"))
    )
    (net (code "56") (name "Net-(C134-Pad2)") (class "Default")
      (node (ref "C134") (pin "2") (pinfunction "2_2") (pintype "passive"))
      (node (ref "R102") (pin "2") (pinfunction "2_2") (pintype "passive"))
      (node (ref "R99") (pin "2") (pinfunction "2_2") (pintype "passive"))
    )
    (net (code "57") (name "Net-(C135-Pad2)") (class "Default")
      (node (ref "C135") (pin "2") (pinfunction "2_2") (pintype "passive"))
      (node (ref "R104") (pin "2") (pinfunction "2_2") (pintype "passive"))
    )
    (net (code "58") (name "Net-(DA8A-AT3VCC)") (class "Default")
      (node (ref "C121") (pin "1") (pinfunction "1_1") (pintype "passive"))
      (node (ref "DA8") (pin "8") (pinfunction "AT3VCC_8") (pintype "passive"))
    )
    (net (code "59") (name "Net-(DA8A-BIN)") (class "Default")
      (node (ref "C122") (pin "1") (pinfunction "1_1") (pintype "passive"))
      (node (ref "DA8") (pin "2") (pinfunction "BIN_2") (pintype "passive"))
    )
    (net (code "60") (name "Net-(DA8A-GIN)") (class "Default")
      (node (ref "C132") (pin "1") (pinfunction "1_1") (pintype "passive"))
      (node (ref "DA8") (pin "13") (pinfunction "GIN_13") (pintype "passive"))
    )
    (net (code "61") (name "Net-(DA8A-RBIAS_EXT)") (class "Default")
      (node (ref "DA8") (pin "9") (pinfunction "RBIAS_EXT_9") (pintype "passive"))
      (node (ref "R93") (pin "2") (pinfunction "2_2") (pintype "passive"))
    )
    (net (code "62") (name "Net-(DA8A-REF_B)") (class "Default")
      (node (ref "C129") (pin "1") (pinfunction "1_1") (pintype "passive"))
      (node (ref "DA8") (pin "4") (pinfunction "REF_B_4") (pintype "passive"))
    )
    (net (code "63") (name "Net-(DA8A-REF_G)") (class "Default")
      (node (ref "C133") (pin "1") (pinfunction "1_1") (pintype "passive"))
      (node (ref "DA8") (pin "15") (pinfunction "REF_G_15") (pintype "passive"))
    )
    (net (code "64") (name "Net-(DA8A-RIN)") (class "Default")
      (node (ref "C134") (pin "1") (pinfunction "1_1") (pintype "passive"))
      (node (ref "DA8") (pin "20") (pinfunction "RIN_20") (pintype "passive"))
    )
    (net (code "65") (name "Net-(DA8A-SOGIN)") (class "Default")
      (node (ref "C130") (pin "1") (pinfunction "1_1") (pintype "passive"))
      (node (ref "DA8") (pin "11") (pinfunction "SOGIN_11") (pintype "passive"))
    )
    (net (code "66") (name "Net-(DA8B-REF_R)") (class "Default")
      (node (ref "C135") (pin "1") (pinfunction "1_1") (pintype "passive"))
      (node (ref "DA8") (pin "22") (pinfunction "REF_R_22") (pintype "passive"))
    )
    (net (code "67") (name "Net-(DA8B-TVCC-Pad26)") (class "Default")
      (node (ref "DA8") (pin "26") (pinfunction "TVCC_26") (pintype "passive"))
      (node (ref "DA8") (pin "38") (pinfunction "TVCC_38") (pintype "passive"))
    )
    (net (code "68") (name "Net-(DA8C-CLK)") (class "Default")
      (node (ref "C139") (pin "2") (pinfunction "2_2") (pintype "passive"))
      (node (ref "DA8") (pin "47") (pinfunction "CLK_47") (pintype "passive"))
      (node (ref "R112") (pin "2") (pinfunction "2_2") (pintype "passive"))
    )
    (net (code "69") (name "Net-(DA8C-CSG0)") (class "Default")
      (node (ref "DA8") (pin "53") (pinfunction "CSG0_53") (pintype "passive"))
      (node (ref "R115") (pin "2") (pinfunction "2_2") (pintype "passive"))
    )
    (net (code "70") (name "Net-(DA8C-CSG1)") (class "Default")
      (node (ref "DA8") (pin "54") (pinfunction "CSG1_54") (pintype "passive"))
      (node (ref "R116") (pin "2") (pinfunction "2_2") (pintype "passive"))
    )
    (net (code "71") (name "Net-(DA8C-HSCL)") (class "Default")
      (node (ref "DA8") (pin "44") (pinfunction "HSCL_44") (pintype "passive"))
      (node (ref "R111") (pin "2") (pinfunction "2_2") (pintype "passive"))
    )
    (net (code "72") (name "Net-(DA8C-HSDA)") (class "Default")
      (node (ref "DA8") (pin "43") (pinfunction "HSDA_43") (pintype "passive"))
      (node (ref "R109") (pin "2") (pinfunction "2_2") (pintype "passive"))
    )
    (net (code "73") (name "Net-(DA8C-INTn)") (class "Default")
      (node (ref "DA8") (pin "50") (pinfunction "INTn_50") (pintype "passive"))
      (node (ref "R113") (pin "2") (pinfunction "2_2") (pintype "passive"))
    )
    (net (code "74") (name "Net-(DA8C-IOVCC-Pad49)") (class "Default")
      (node (ref "DA8") (pin "49") (pinfunction "IOVCC_49") (pintype "passive"))
      (node (ref "DA8") (pin "57") (pinfunction "IOVCC_57") (pintype "passive"))
      (node (ref "DA8") (pin "67") (pinfunction "IOVCC_67") (pintype "passive"))
      (node (ref "DA8") (pin "79") (pinfunction "IOVCC_79") (pintype "passive"))
    )
    (net (code "75") (name "Net-(DA8C-PA0)") (class "Default")
      (node (ref "DA8") (pin "58") (pinfunction "PA0_58") (pintype "passive"))
      (node (ref "R117") (pin "2") (pinfunction "2_2") (pintype "passive"))
    )
    (net (code "76") (name "Net-(DA8C-PA1)") (class "Default")
      (node (ref "DA8") (pin "59") (pinfunction "PA1_59") (pintype "passive"))
      (node (ref "R118") (pin "2") (pinfunction "2_2") (pintype "passive"))
    )
    (net (code "77") (name "Net-(DA8C-PA2)") (class "Default")
      (node (ref "DA8") (pin "60") (pinfunction "PA2_60") (pintype "passive"))
      (node (ref "R120") (pin "2") (pinfunction "2_2") (pintype "passive"))
    )
    (net (code "78") (name "Net-(DA8C-PCLK)") (class "Default")
      (node (ref "DA8") (pin "52") (pinfunction "PCLK_52") (pintype "passive"))
      (node (ref "R114") (pin "2") (pinfunction "2_2") (pintype "passive"))
    )
    (net (code "79") (name "Net-(DA8D-PA3)") (class "Default")
      (node (ref "DA8") (pin "61") (pinfunction "PA3_61") (pintype "passive"))
      (node (ref "R122") (pin "2") (pinfunction "2_2") (pintype "passive"))
    )
    (net (code "80") (name "Net-(DA8D-PA4)") (class "Default")
      (node (ref "DA8") (pin "62") (pinfunction "PA4_62") (pintype "passive"))
      (node (ref "R125") (pin "2") (pinfunction "2_2") (pintype "passive"))
    )
    (net (code "81") (name "Net-(DA8D-PA5)") (class "Default")
      (node (ref "DA8") (pin "63") (pinfunction "PA5_63") (pintype "passive"))
      (node (ref "R128") (pin "2") (pinfunction "2_2") (pintype "passive"))
    )
    (net (code "82") (name "Net-(DA8D-PA6)") (class "Default")
      (node (ref "DA8") (pin "64") (pinfunction "PA6_64") (pintype "passive"))
      (node (ref "R131") (pin "2") (pinfunction "2_2") (pintype "passive"))
    )
    (net (code "83") (name "Net-(DA8D-PA7)") (class "Default")
      (node (ref "DA8") (pin "65") (pinfunction "PA7_65") (pintype "passive"))
      (node (ref "R134") (pin "2") (pinfunction "2_2") (pintype "passive"))
    )
    (net (code "84") (name "Net-(DA8D-PB0)") (class "Default")
      (node (ref "DA8") (pin "68") (pinfunction "PB0_68") (pintype "passive"))
      (node (ref "R119") (pin "2") (pinfunction "2_2") (pintype "passive"))
    )
    (net (code "85") (name "Net-(DA8D-PB1)") (class "Default")
      (node (ref "DA8") (pin "69") (pinfunction "PB1_69") (pintype "passive"))
      (node (ref "R121") (pin "2") (pinfunction "2_2") (pintype "passive"))
    )
    (net (code "86") (name "Net-(DA8D-PB2)") (class "Default")
      (node (ref "DA8") (pin "72") (pinfunction "PB2_72") (pintype "passive"))
      (node (ref "R124") (pin "2") (pinfunction "2_2") (pintype "passive"))
    )
    (net (code "87") (name "Net-(DA8D-PB3)") (class "Default")
      (node (ref "DA8") (pin "73") (pinfunction "PB3_73") (pintype "passive"))
      (node (ref "R127") (pin "2") (pinfunction "2_2") (pintype "passive"))
    )
    (net (code "88") (name "Net-(DA8D-PB4)") (class "Default")
      (node (ref "DA8") (pin "74") (pinfunction "PB4_74") (pintype "passive"))
      (node (ref "R130") (pin "2") (pinfunction "2_2") (pintype "passive"))
    )
    (net (code "89") (name "Net-(DA8D-PB5)") (class "Default")
      (node (ref "DA8") (pin "75") (pinfunction "PB5_75") (pintype "passive"))
      (node (ref "R133") (pin "2") (pinfunction "2_2") (pintype "passive"))
    )
    (net (code "90") (name "Net-(DA8D-PB6)") (class "Default")
      (node (ref "DA8") (pin "76") (pinfunction "PB6_76") (pintype "passive"))
      (node (ref "R136") (pin "2") (pinfunction "2_2") (pintype "passive"))
    )
    (net (code "91") (name "Net-(DA8D-PB7)") (class "Default")
      (node (ref "DA8") (pin "77") (pinfunction "PB7_77") (pintype "passive"))
      (node (ref "R138") (pin "2") (pinfunction "2_2") (pintype "passive"))
    )
    (net (code "92") (name "Net-(DA8D-PC0)") (class "Default")
      (node (ref "DA8") (pin "80") (pinfunction "PC0_80") (pintype "passive"))
      (node (ref "R140") (pin "1") (pinfunction "1_1") (pintype "passive"))
    )
    (net (code "93") (name "Net-(DA8E-PC1)") (class "Default")
      (node (ref "DA8") (pin "81") (pinfunction "PC1_81") (pintype "passive"))
      (node (ref "R139") (pin "1") (pinfunction "1_1") (pintype "passive"))
    )
    (net (code "94") (name "Net-(DA8E-PC2)") (class "Default")
      (node (ref "DA8") (pin "82") (pinfunction "PC2_82") (pintype "passive"))
      (node (ref "R137") (pin "1") (pinfunction "1_1") (pintype "passive"))
    )
    (net (code "95") (name "Net-(DA8E-PC3)") (class "Default")
      (node (ref "DA8") (pin "83") (pinfunction "PC3_83") (pintype "passive"))
      (node (ref "R135") (pin "1") (pinfunction "1_1") (pintype "passive"))
    )
    (net (code "96") (name "Net-(DA8E-PC4)") (class "Default")
      (node (ref "DA8") (pin "84") (pinfunction "PC4_84") (pintype "passive"))
      (node (ref "R132") (pin "1") (pinfunction "1_1") (pintype "passive"))
    )
    (net (code "97") (name "Net-(DA8E-PC5)") (class "Default")
      (node (ref "DA8") (pin "85") (pinfunction "PC5_85") (pintype "passive"))
      (node (ref "R129") (pin "1") (pinfunction "1_1") (pintype "passive"))
    )
    (net (code "98") (name "Net-(DA8E-PC6)") (class "Default")
      (node (ref "DA8") (pin "86") (pinfunction "PC6_86") (pintype "passive"))
      (node (ref "R126") (pin "1") (pinfunction "1_1") (pintype "passive"))
    )
    (net (code "99") (name "Net-(DA8E-PC7)") (class "Default")
      (node (ref "DA8") (pin "87") (pinfunction "PC7_87") (pintype "passive"))
      (node (ref "R123") (pin "1") (pinfunction "1_1") (pintype "passive"))
    )
    (net (code "100") (name "Net-(DA8G-CSG3)") (class "Default")
      (node (ref "DA8") (pin "126") (pinfunction "CSG3_126") (pintype "passive"))
      (node (ref "R108") (pin "1") (pinfunction "1_1") (pintype "passive"))
    )
    (net (code "101") (name "Net-(DA8G-PWM)") (class "Default")
      (node (ref "DA8") (pin "139") (pinfunction "PWM_139") (pintype "passive"))
      (node (ref "R101") (pin "1") (pinfunction "1_1") (pintype "passive"))
      (node (ref "R103") (pin "1") (pinfunction "1_1") (pintype "passive"))
    )
    (net (code "102") (name "Net-(DA8G-VCLK)") (class "Default")
      (node (ref "DA8") (pin "135") (pinfunction "VCLK_135") (pintype "passive"))
      (node (ref "R106") (pin "1") (pinfunction "1_1") (pintype "passive"))
    )
    (net (code "103") (name "Net-(DA8H-A3V3VCC)") (class "Default")
      (node (ref "C109") (pin "2") (pinfunction "2_2") (pintype "passive"))
      (node (ref "C110") (pin "2") (pinfunction "2_2") (pintype "passive"))
      (node (ref "C111") (pin "2") (pinfunction "2_2") (pintype "passive"))
      (node (ref "DA8") (pin "159") (pinfunction "A3V3VCC_159") (pintype "passive"))
      (node (ref "L35") (pin "2") (pinfunction "2_2") (pintype "passive"))
      (node (ref "R88") (pin "2") (pinfunction "2_2") (pintype "passive"))
    )
    (net (code "104") (name "Net-(DA8H-AGC_ANA)") (class "Default")
      (node (ref "DA8") (pin "160") (pinfunction "AGC_ANA_160") (pintype "passive"))
      (node (ref "R91") (pin "2") (pinfunction "2_2") (pintype "passive"))
    )
    (net (code "105") (name "Net-(DA8H-LLPLLAGND)") (class "Default")
      (node (ref "C123") (pin "1") (pinfunction "1_1") (pintype "passive"))
      (node (ref "C128") (pin "2") (pinfunction "2_2") (pintype "passive"))
      (node (ref "C131") (pin "2") (pinfunction "2_2") (pintype "passive"))
      (node (ref "DA8") (pin "149") (pinfunction "LLPLLAGND_149") (pintype "passive"))
    )
    (net (code "106") (name "Net-(DA8H-LLPLLAVCC)") (class "Default")
      (node (ref "C123") (pin "2") (pinfunction "2_2") (pintype "passive"))
      (node (ref "C128") (pin "1") (pinfunction "1_1") (pintype "passive"))
      (node (ref "C131") (pin "1") (pinfunction "1_1") (pintype "passive"))
      (node (ref "DA8") (pin "150") (pinfunction "LLPLLAVCC_150") (pintype "passive"))
      (node (ref "L38") (pin "2") (pinfunction "2_2") (pintype "passive"))
    )
    (net (code "107") (name "Net-(DD3-VIN)") (class "Default")
      (node (ref "C147") (pin "2") (pinfunction "2_2") (pintype "passive"))
      (node (ref "C148") (pin "2") (pinfunction "2_2") (pintype "passive"))
      (node (ref "DD3") (pin "1") (pinfunction "VIN_1") (pintype "passive"))
      (node (ref "L47") (pin "2") (pinfunction "2_2") (pintype "passive"))
      (node (ref "VD24") (pin "1") (pinfunction "1_1") (pintype "passive"))
    )
    (net (code "108") (name "Net-(DD3-VOUT)") (class "Default")
      (node (ref "C149") (pin "2") (pinfunction "2_2") (pintype "passive"))
      (node (ref "C150") (pin "2") (pinfunction "2_2") (pintype "passive"))
      (node (ref "DD3") (pin "2") (pinfunction "VOUT_2") (pintype "passive"))
      (node (ref "L45") (pin "1") (pinfunction "1_1") (pintype "passive"))
      (node (ref "VD24") (pin "2") (pinfunction "2_2") (pintype "passive"))
    )
    (net (code "109") (name "Net-(G1-OUT)") (class "Default")
      (node (ref "G1") (pin "3") (pinfunction "OUT_3") (pintype "passive"))
      (node (ref "R112") (pin "1") (pinfunction "1_1") (pintype "passive"))
    )
    (net (code "110") (name "Net-(G1-VCC)") (class "Default")
      (node (ref "C137") (pin "2") (pinfunction "2_2") (pintype "passive"))
      (node (ref "C138") (pin "2") (pinfunction "2_2") (pintype "passive"))
      (node (ref "G1") (pin "4") (pinfunction "VCC_4") (pintype "passive"))
      (node (ref "L42") (pin "2") (pinfunction "2_2") (pintype "passive"))
    )
    (net (code "111") (name "Net-(L40-Pad1)") (class "Default")
      (node (ref "L40") (pin "1") (pinfunction "1_1") (pintype "passive"))
      (node (ref "VT13") (pin "3") (pinfunction "3_3") (pintype "passive"))
      (node (ref "VT13") (pin "4") (pinfunction "4_4") (pintype "passive"))
    )
    (net (code "112") (name "Net-(L41-Pad1)") (class "Default")
      (node (ref "L41") (pin "1") (pinfunction "1_1") (pintype "passive"))
      (node (ref "VT13") (pin "2") (pinfunction "2_2") (pintype "passive"))
    )
    (net (code "113") (name "Net-(R88-Pad1)") (class "Default")
      (node (ref "R88") (pin "1") (pinfunction "1_1") (pintype "passive"))
      (node (ref "VD23") (pin "2") (pinfunction "2_2") (pintype "passive"))
    )
    (net (code "114") (name "Net-(VT14-BAZA)") (class "Default")
      (node (ref "R100") (pin "2") (pinfunction "2_2") (pintype "passive"))
      (node (ref "R105") (pin "2") (pinfunction "2_2") (pintype "passive"))
      (node (ref "VT14") (pin "3") (pinfunction "BAZA_3") (pintype "passive"))
    )
    (net (code "115") (name "Net-(VT14-EMITTER)") (class "Default")
      (node (ref "R94") (pin "1") (pinfunction "1_1") (pintype "passive"))
      (node (ref "VT13") (pin "1") (pinfunction "1_1") (pintype "passive"))
      (node (ref "VT14") (pin "2") (pinfunction "EMITTER_2") (pintype "passive"))
    )
    (net (code "116") (name "Net-(VT15-BAZA)") (class "Default")
      (node (ref "R103") (pin "2") (pinfunction "2_2") (pintype "passive"))
      (node (ref "R107") (pin "2") (pinfunction "2_2") (pintype "passive"))
      (node (ref "VT15") (pin "3") (pinfunction "BAZA_3") (pintype "passive"))
    )
    (net (code "117") (name "VCC") (class "Default")
      (node (ref "C100") (pin "2") (pinfunction "2_2") (pintype "passive"))
      (node (ref "C101") (pin "2") (pinfunction "2_2") (pintype "passive"))
      (node (ref "C102") (pin "2") (pinfunction "2_2") (pintype "passive"))
      (node (ref "C103") (pin "2") (pinfunction "2_2") (pintype "passive"))
      (node (ref "C104") (pin "2") (pinfunction "2_2") (pintype "passive"))
      (node (ref "C105") (pin "2") (pinfunction "2_2") (pintype "passive"))
      (node (ref "C106") (pin "2") (pinfunction "2_2") (pintype "passive"))
      (node (ref "C107") (pin "2") (pinfunction "2_2") (pintype "passive"))
      (node (ref "C108") (pin "2") (pinfunction "2_2") (pintype "passive"))
      (node (ref "C112") (pin "2") (pinfunction "2_2") (pintype "passive"))
      (node (ref "C113") (pin "2") (pinfunction "2_2") (pintype "passive"))
      (node (ref "C114") (pin "2") (pinfunction "2_2") (pintype "passive"))
      (node (ref "C115") (pin "2") (pinfunction "2_2") (pintype "passive"))
      (node (ref "C116") (pin "2") (pinfunction "2_2") (pintype "passive"))
      (node (ref "C117") (pin "2") (pinfunction "2_2") (pintype "passive"))
      (node (ref "C118") (pin "2") (pinfunction "2_2") (pintype "passive"))
      (node (ref "C119") (pin "2") (pinfunction "2_2") (pintype "passive"))
      (node (ref "C120") (pin "2") (pinfunction "2_2") (pintype "passive"))
      (node (ref "C124") (pin "2") (pinfunction "2_2") (pintype "passive"))
      (node (ref "C125") (pin "2") (pinfunction "2_2") (pintype "passive"))
      (node (ref "C126") (pin "2") (pinfunction "2_2") (pintype "passive"))
      (node (ref "C127") (pin "2") (pinfunction "2_2") (pintype "passive"))
      (node (ref "C136") (pin "1") (pinfunction "1_1") (pintype "passive"))
      (node (ref "C140") (pin "2") (pinfunction "2_2") (pintype "passive"))
      (node (ref "C141") (pin "2") (pinfunction "2_2") (pintype "passive"))
      (node (ref "C142") (pin "2") (pinfunction "2_2") (pintype "passive"))
      (node (ref "C143") (pin "2") (pinfunction "2_2") (pintype "passive"))
      (node (ref "C144") (pin "2") (pinfunction "2_2") (pintype "passive"))
      (node (ref "C145") (pin "2") (pinfunction "2_2") (pintype "passive"))
      (node (ref "C146") (pin "2") (pinfunction "2_2") (pintype "passive"))
      (node (ref "C97") (pin "2") (pinfunction "2_2") (pintype "passive"))
      (node (ref "C98") (pin "2") (pinfunction "2_2") (pintype "passive"))
      (node (ref "C99") (pin "2") (pinfunction "2_2") (pintype "passive"))
      (node (ref "DA8") (pin "101") (pinfunction "IOVCC_101") (pintype "passive"))
      (node (ref "DA8") (pin "103") (pinfunction "CVCC_103") (pintype "passive"))
      (node (ref "DA8") (pin "113") (pinfunction "IOVCC_113") (pintype "passive"))
      (node (ref "DA8") (pin "123") (pinfunction "CVCC_123") (pintype "passive"))
      (node (ref "DA8") (pin "125") (pinfunction "IOVCC_125") (pintype "passive"))
      (node (ref "DA8") (pin "132") (pinfunction "IOVCC_132") (pintype "passive"))
      (node (ref "DA8") (pin "143") (pinfunction "IOVCC_143") (pintype "passive"))
      (node (ref "DA8") (pin "145") (pinfunction "CVCC_145") (pintype "passive"))
      (node (ref "DA8") (pin "147") (pinfunction "PLLVCC_147") (pintype "passive"))
      (node (ref "DA8") (pin "152") (pinfunction "LLPLLVCC_152") (pintype "passive"))
      (node (ref "DA8") (pin "17") (pinfunction "AVCC_G_17") (pintype "passive"))
      (node (ref "DA8") (pin "24") (pinfunction "AVCC_R_24") (pintype "passive"))
      (node (ref "DA8") (pin "29") (pinfunction "TGND_29") (pintype "passive"))
      (node (ref "DA8") (pin "35") (pinfunction "TGND_35") (pintype "passive"))
      (node (ref "DA8") (pin "39") (pinfunction "TPLLGND_39") (pintype "passive"))
      (node (ref "DA8") (pin "40") (pinfunction "TPLLVCC_40") (pintype "passive"))
      (node (ref "DA8") (pin "6") (pinfunction "AVCC_B_6") (pintype "passive"))
      (node (ref "DA8") (pin "89") (pinfunction "IOVCC_89") (pintype "passive"))
      (node (ref "DA8") (pin "91") (pinfunction "CVCC_91") (pintype "passive"))
      (node (ref "L34") (pin "1") (pinfunction "1_1") (pintype "passive"))
      (node (ref "L34") (pin "2") (pinfunction "2_2") (pintype "passive"))
      (node (ref "L35") (pin "1") (pinfunction "1_1") (pintype "passive"))
      (node (ref "L36") (pin "1") (pinfunction "1_1") (pintype "passive"))
      (node (ref "L36") (pin "2") (pinfunction "2_2") (pintype "passive"))
      (node (ref "L37") (pin "1") (pinfunction "1_1") (pintype "passive"))
      (node (ref "L37") (pin "2") (pinfunction "2_2") (pintype "passive"))
      (node (ref "L38") (pin "1") (pinfunction "1_1") (pintype "passive"))
      (node (ref "L39") (pin "1") (pinfunction "1_1") (pintype "passive"))
      (node (ref "L39") (pin "2") (pinfunction "2_2") (pintype "passive"))
      (node (ref "L40") (pin "2") (pinfunction "2_2") (pintype "passive"))
      (node (ref "L41") (pin "2") (pinfunction "2_2") (pintype "passive"))
      (node (ref "L42") (pin "1") (pinfunction "1_1") (pintype "passive"))
      (node (ref "L43") (pin "1") (pinfunction "1_1") (pintype "passive"))
      (node (ref "L43") (pin "2") (pinfunction "2_2") (pintype "passive"))
      (node (ref "L44") (pin "1") (pinfunction "1_1") (pintype "passive"))
      (node (ref "L44") (pin "2") (pinfunction "2_2") (pintype "passive"))
      (node (ref "L45") (pin "2") (pinfunction "2_2") (pintype "passive"))
      (node (ref "L47") (pin "1") (pinfunction "1_1") (pintype "passive"))
      (node (ref "R101") (pin "2") (pinfunction "2_2") (pintype "passive"))
      (node (ref "R94") (pin "2") (pinfunction "2_2") (pintype "passive"))
      (node (ref "R97") (pin "2") (pinfunction "2_2") (pintype "passive"))
    )
    (net (code "118") (name "unconnected-(DA8B-TVCC-Pad32)") (class "Default")
      (node (ref "DA8") (pin "32") (pinfunction "TVCC_32") (pintype "passive+no_connect"))
    )
    (net (code "119") (name "unconnected-(DA8E-PD0-Pad92)") (class "Default")
      (node (ref "DA8") (pin "92") (pinfunction "PD0_92") (pintype "passive"))
    )
    (net (code "120") (name "unconnected-(DA8E-PD1-Pad93)") (class "Default")
      (node (ref "DA8") (pin "93") (pinfunction "PD1_93") (pintype "passive"))
    )
    (net (code "121") (name "unconnected-(DA8E-PD2-Pad94)") (class "Default")
      (node (ref "DA8") (pin "94") (pinfunction "PD2_94") (pintype "passive"))
    )
    (net (code "122") (name "unconnected-(DA8E-PD3-Pad95)") (class "Default")
      (node (ref "DA8") (pin "95") (pinfunction "PD3_95") (pintype "passive"))
    )
    (net (code "123") (name "unconnected-(DA8E-PD4-Pad96)") (class "Default")
      (node (ref "DA8") (pin "96") (pinfunction "PD4_96") (pintype "passive"))
    )
    (net (code "124") (name "unconnected-(DA8E-PD5-Pad97)") (class "Default")
      (node (ref "DA8") (pin "97") (pinfunction "PD5_97") (pintype "passive"))
    )
    (net (code "125") (name "unconnected-(DA8E-PD6-Pad98)") (class "Default")
      (node (ref "DA8") (pin "98") (pinfunction "PD6_98") (pintype "passive"))
    )
    (net (code "126") (name "unconnected-(DA8E-PD7-Pad99)") (class "Default")
      (node (ref "DA8") (pin "99") (pinfunction "PD7_99") (pintype "passive"))
    )
    (net (code "127") (name "unconnected-(DA8F-PE0-Pad104)") (class "Default")
      (node (ref "DA8") (pin "104") (pinfunction "PE0_104") (pintype "passive"))
    )
    (net (code "128") (name "unconnected-(DA8F-PE1-Pad105)") (class "Default")
      (node (ref "DA8") (pin "105") (pinfunction "PE1_105") (pintype "passive"))
    )
    (net (code "129") (name "unconnected-(DA8F-PE2-Pad106)") (class "Default")
      (node (ref "DA8") (pin "106") (pinfunction "PE2_106") (pintype "passive"))
    )
    (net (code "130") (name "unconnected-(DA8F-PE3-Pad107)") (class "Default")
      (node (ref "DA8") (pin "107") (pinfunction "PE3_107") (pintype "passive"))
    )
    (net (code "131") (name "unconnected-(DA8F-PE4-Pad108)") (class "Default")
      (node (ref "DA8") (pin "108") (pinfunction "PE4_108") (pintype "passive"))
    )
    (net (code "132") (name "unconnected-(DA8F-PE5-Pad109)") (class "Default")
      (node (ref "DA8") (pin "109") (pinfunction "PE5_109") (pintype "passive"))
    )
    (net (code "133") (name "unconnected-(DA8F-PE6-Pad110)") (class "Default")
      (node (ref "DA8") (pin "110") (pinfunction "PE6_110") (pintype "passive"))
    )
    (net (code "134") (name "unconnected-(DA8F-PE7-Pad111)") (class "Default")
      (node (ref "DA8") (pin "111") (pinfunction "PE7_111") (pintype "passive"))
    )
    (net (code "135") (name "unconnected-(DA8F-PF0-Pad114)") (class "Default")
      (node (ref "DA8") (pin "114") (pinfunction "PF0_114") (pintype "passive"))
    )
    (net (code "136") (name "unconnected-(DA8F-PF1-Pad115)") (class "Default")
      (node (ref "DA8") (pin "115") (pinfunction "PF1_115") (pintype "passive"))
    )
    (net (code "137") (name "unconnected-(DA8F-PF2-Pad116)") (class "Default")
      (node (ref "DA8") (pin "116") (pinfunction "PF2_116") (pintype "passive"))
    )
    (net (code "138") (name "unconnected-(DA8F-PF3-Pad117)") (class "Default")
      (node (ref "DA8") (pin "117") (pinfunction "PF3_117") (pintype "passive"))
    )
    (net (code "139") (name "unconnected-(DA8F-PF4-Pad118)") (class "Default")
      (node (ref "DA8") (pin "118") (pinfunction "PF4_118") (pintype "passive"))
    )
    (net (code "140") (name "unconnected-(DA8F-PF5-Pad119)") (class "Default")
      (node (ref "DA8") (pin "119") (pinfunction "PF5_119") (pintype "passive"))
    )
    (net (code "141") (name "unconnected-(DA8F-PF6-Pad120)") (class "Default")
      (node (ref "DA8") (pin "120") (pinfunction "PF6_120") (pintype "passive"))
    )
    (net (code "142") (name "unconnected-(DA8G-CSG5-Pad128)") (class "Default")
      (node (ref "DA8") (pin "128") (pinfunction "CSG5_128") (pintype "passive"))
    )
    (net (code "143") (name "unconnected-(DA8G-CSG6-Pad129)") (class "Default")
      (node (ref "DA8") (pin "129") (pinfunction "CSG6_129") (pintype "passive"))
    )
    (net (code "144") (name "unconnected-(DA8G-CSG7-Pad130)") (class "Default")
      (node (ref "DA8") (pin "130") (pinfunction "CSG7_130") (pintype "passive"))
    )
    (net (code "145") (name "unconnected-(DA8G-CSG8-Pad133)") (class "Default")
      (node (ref "DA8") (pin "133") (pinfunction "CSG8_133") (pintype "passive"))
    )
    (net (code "146") (name "unconnected-(DA8G-CSG9-Pad134)") (class "Default")
      (node (ref "DA8") (pin "134") (pinfunction "CSG9_134") (pintype "passive"))
    )
    (net (code "147") (name "unconnected-(DA8G-INVA-Pad136)") (class "Default")
      (node (ref "DA8") (pin "136") (pinfunction "INVA_136") (pintype "passive"))
    )
    (net (code "148") (name "unconnected-(DA8G-INVB-Pad137)") (class "Default")
      (node (ref "DA8") (pin "137") (pinfunction "INVB_137") (pintype "passive"))
    )
    (net (code "149") (name "unconnected-(DA8G-OUTEN-Pad138)") (class "Default")
      (node (ref "DA8") (pin "138") (pinfunction "OUTEN_138") (pintype "passive"))
    )
    (net (code "150") (name "unconnected-(DA8G-PF7-Pad121)") (class "Default")
      (node (ref "DA8") (pin "121") (pinfunction "PF7_121") (pintype "passive"))
    )
    (net (code "151") (name "unconnected-(DA8H-NC-Pad148)") (class "Default")
      (node (ref "DA8") (pin "148") (pinfunction "NC_148") (pintype "passive"))
    )
    (net (code "152") (name "unconnected-(DA8H-TDO-Pad157)") (class "Default")
      (node (ref "DA8") (pin "157") (pinfunction "TDO_157") (pintype "passive"))
    )
    (net (code "153") (name "unconnected-(G1-NC-Pad1)") (class "Default")
      (node (ref "G1") (pin "1") (pinfunction "NC_1") (pintype "passive+no_connect"))
    )
  )
)
